# io_conn.net
KiCad netlist of a schematic drawn in Altium Designer
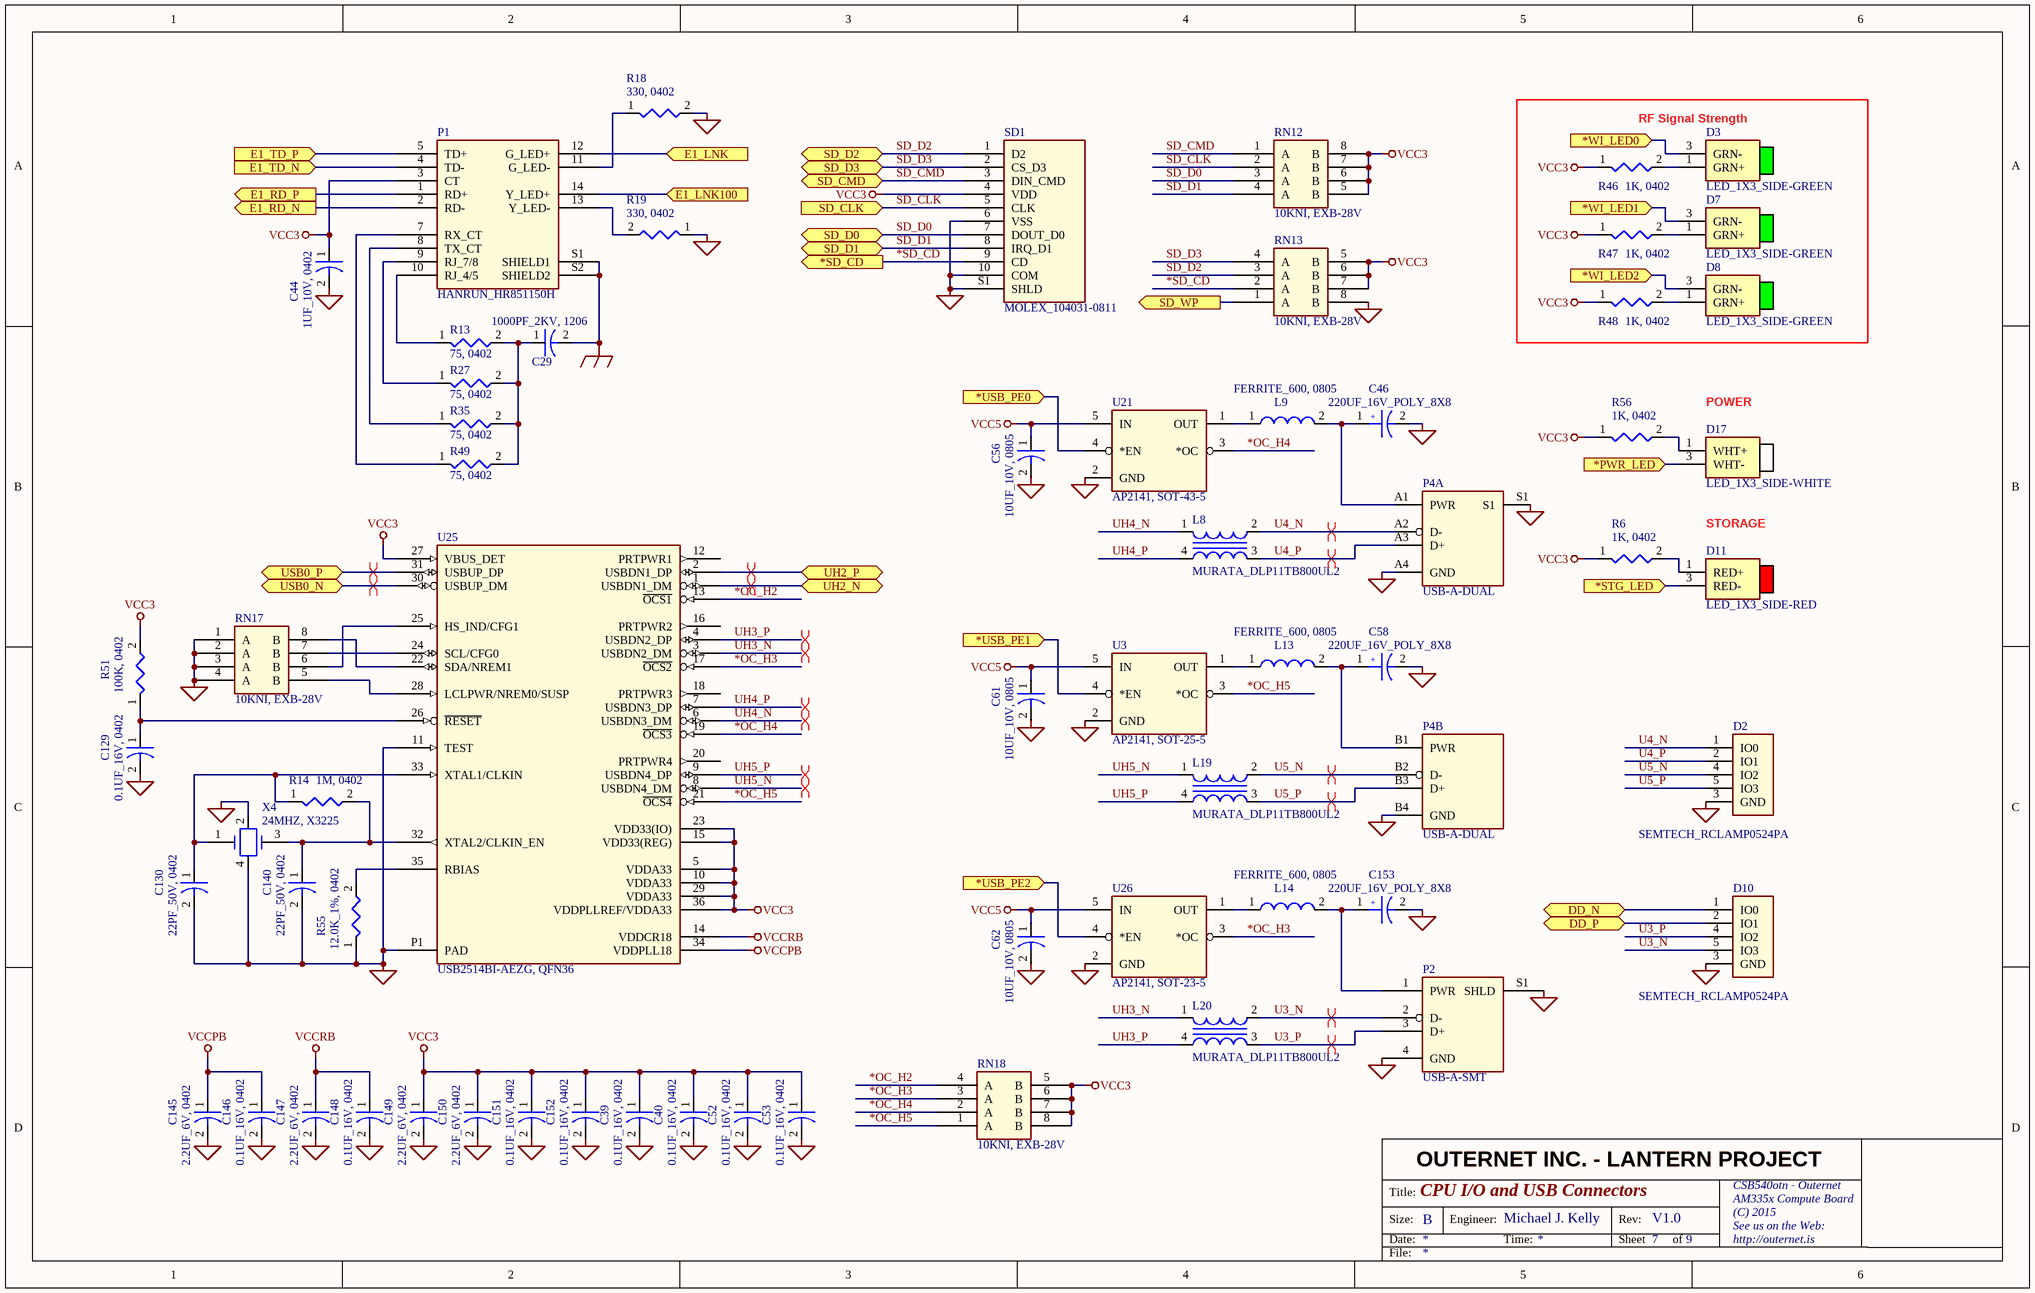
[diagram p0: io_conn.SchDoc]

(export (version "E")
  (design (tool "Eeschema 10.0.6"))
  (components
    (comp (ref "C29")
      (value "1000PF_2KV, 1206")
      (footprint "1206C")
      (description "CAP - 1206 PKG")
      (libsource (lib "COGENT_Library") (part "1000PF_2KV, 1206"))
    )
    (comp (ref "C39")
      (value "0.1UF_16V, 0402")
      (footprint "0402C")
      (description "CAP - 0402 PKG")
      (libsource (lib "COGENT_Library") (part "0.1UF_16V, 0402"))
    )
    (comp (ref "C40")
      (value "0.1UF_16V, 0402")
      (footprint "0402C")
      (description "CAP - 0402 PKG")
      (libsource (lib "COGENT_Library") (part "0.1UF_16V, 0402"))
    )
    (comp (ref "C44")
      (value "1UF_10V, 0402")
      (footprint "0402C")
      (description "CAP - 0402 PKG")
      (libsource (lib "COGENT_Library") (part "1UF_10V, 0402"))
    )
    (comp (ref "C46")
      (value "220UF_16V_POLY_8X8")
      (footprint "ELEC_8MM_8MM")
      (description "CAP - ELEC_POLY, 8mm x 8mm x 3.5mm")
      (libsource (lib "COGENT_Library") (part "220UF_16V_POLY_8X8"))
    )
    (comp (ref "C52")
      (value "0.1UF_16V, 0402")
      (footprint "0402C")
      (description "CAP - 0402 PKG")
      (libsource (lib "COGENT_Library") (part "0.1UF_16V, 0402"))
    )
    (comp (ref "C53")
      (value "0.1UF_16V, 0402")
      (footprint "0402C")
      (description "CAP - 0402 PKG")
      (libsource (lib "COGENT_Library") (part "0.1UF_16V, 0402"))
    )
    (comp (ref "C56")
      (value "10UF_10V, 0805")
      (footprint "0805C")
      (description "CAP - 0805 PKG")
      (libsource (lib "COGENT_Library") (part "10UF_10V, 0805"))
    )
    (comp (ref "C58")
      (value "220UF_16V_POLY_8X8")
      (footprint "ELEC_8MM_8MM")
      (description "CAP - ELEC_POLY, 8mm x 8mm x 3.5mm")
      (libsource (lib "COGENT_Library") (part "220UF_16V_POLY_8X8"))
    )
    (comp (ref "C61")
      (value "10UF_10V, 0805")
      (footprint "0805C")
      (description "CAP - 0805 PKG")
      (libsource (lib "COGENT_Library") (part "10UF_10V, 0805"))
    )
    (comp (ref "C62")
      (value "10UF_10V, 0805")
      (footprint "0805C")
      (description "CAP - 0805 PKG")
      (libsource (lib "COGENT_Library") (part "10UF_10V, 0805"))
    )
    (comp (ref "C129")
      (value "0.1UF_16V, 0402")
      (footprint "0402C")
      (description "CAP - 0402 PKG")
      (libsource (lib "COGENT_Library") (part "0.1UF_16V, 0402"))
    )
    (comp (ref "C130")
      (value "22PF_50V, 0402")
      (footprint "0402C")
      (description "CAP - 0402 PKG")
      (libsource (lib "COGENT_Library") (part "22PF_50V, 0402"))
    )
    (comp (ref "C140")
      (value "22PF_50V, 0402")
      (footprint "0402C")
      (description "CAP - 0402 PKG")
      (libsource (lib "COGENT_Library") (part "22PF_50V, 0402"))
    )
    (comp (ref "C145")
      (value "2.2UF_6V, 0402")
      (footprint "0402C")
      (description "CAP - 0402 PKG")
      (libsource (lib "COGENT_Library") (part "2.2UF_6V, 0402"))
    )
    (comp (ref "C146")
      (value "0.1UF_16V, 0402")
      (footprint "0402C")
      (description "CAP - 0402 PKG")
      (libsource (lib "COGENT_Library") (part "0.1UF_16V, 0402"))
    )
    (comp (ref "C147")
      (value "2.2UF_6V, 0402")
      (footprint "0402C")
      (description "CAP - 0402 PKG")
      (libsource (lib "COGENT_Library") (part "2.2UF_6V, 0402"))
    )
    (comp (ref "C148")
      (value "0.1UF_16V, 0402")
      (footprint "0402C")
      (description "CAP - 0402 PKG")
      (libsource (lib "COGENT_Library") (part "0.1UF_16V, 0402"))
    )
    (comp (ref "C149")
      (value "2.2UF_6V, 0402")
      (footprint "0402C")
      (description "CAP - 0402 PKG")
      (libsource (lib "COGENT_Library") (part "2.2UF_6V, 0402"))
    )
    (comp (ref "C150")
      (value "2.2UF_6V, 0402")
      (footprint "0402C")
      (description "CAP - 0402 PKG")
      (libsource (lib "COGENT_Library") (part "2.2UF_6V, 0402"))
    )
    (comp (ref "C151")
      (value "0.1UF_16V, 0402")
      (footprint "0402C")
      (description "CAP - 0402 PKG")
      (libsource (lib "COGENT_Library") (part "0.1UF_16V, 0402"))
    )
    (comp (ref "C152")
      (value "0.1UF_16V, 0402")
      (footprint "0402C")
      (description "CAP - 0402 PKG")
      (libsource (lib "COGENT_Library") (part "0.1UF_16V, 0402"))
    )
    (comp (ref "C153")
      (value "220UF_16V_POLY_8X8")
      (footprint "ELEC_8MM_8MM")
      (description "CAP - ELEC_POLY, 8mm x 8mm x 3.5mm")
      (libsource (lib "COGENT_Library") (part "220UF_16V_POLY_8X8"))
    )
    (comp (ref "D2")
      (value "SEMTECH_RCLAMP0524PA")
      (footprint "RCLAMP0524")
      (description "DIODE - TVS ARRAY, 0.3PF")
      (libsource (lib "COGENT_Library") (part "SEMTECH_RCLAMP0524PA"))
    )
    (comp (ref "D3")
      (value "LED_1X3_SIDE-GREEN")
      (footprint "LED_1X3_SIDE-GREEN")
      (description "LED - SIDEVIEW, SMT, GREEN")
      (libsource (lib "COGENT_Library") (part "LED_1X3_SIDE-GREEN"))
    )
    (comp (ref "D7")
      (value "LED_1X3_SIDE-GREEN")
      (footprint "LED_1X3_SIDE-GREEN")
      (description "LED - SIDEVIEW, SMT, GREEN")
      (libsource (lib "COGENT_Library") (part "LED_1X3_SIDE-GREEN"))
    )
    (comp (ref "D8")
      (value "LED_1X3_SIDE-GREEN")
      (footprint "LED_1X3_SIDE-GREEN")
      (description "LED - SIDEVIEW, SMT, GREEN")
      (libsource (lib "COGENT_Library") (part "LED_1X3_SIDE-GREEN"))
    )
    (comp (ref "D10")
      (value "SEMTECH_RCLAMP0524PA")
      (footprint "RCLAMP0524")
      (description "DIODE - TVS ARRAY, 0.3PF")
      (libsource (lib "COGENT_Library") (part "SEMTECH_RCLAMP0524PA"))
    )
    (comp (ref "D11")
      (value "LED_1X3_SIDE-RED")
      (footprint "LED_1X3_SIDE-RED")
      (description "LED - SIDEVIEW, SMT, RED")
      (libsource (lib "COGENT_Library") (part "LED_1X3_SIDE-RED"))
    )
    (comp (ref "D17")
      (value "LED_1X3_SIDE-WHITE")
      (footprint "LED_1X3_SIDE-WHITE")
      (description "LED - SIDEVIEW, SMT, WHITE")
      (libsource (lib "COGENT_Library") (part "LED_1X3_SIDE-WHITE"))
    )
    (comp (ref "L8")
      (value "MURATA_DLP11TB800UL2")
      (footprint "PANASONIC_EXC24C")
      (description "FERRITE - COMMON MODE FILTER, USB3, FILM")
      (libsource (lib "COGENT_Library") (part "MURATA_DLP11TB800UL2"))
    )
    (comp (ref "L9")
      (value "FERRITE_600, 0805")
      (footprint "0805L")
      (description "FERRITE BEAD - 600 OHM, 2A, 0805 PKG")
      (libsource (lib "COGENT_Library") (part "FERRITE_600, 0805"))
    )
    (comp (ref "L13")
      (value "FERRITE_600, 0805")
      (footprint "0805L")
      (description "FERRITE BEAD - 600 OHM, 2A, 0805 PKG")
      (libsource (lib "COGENT_Library") (part "FERRITE_600, 0805"))
    )
    (comp (ref "L14")
      (value "FERRITE_600, 0805")
      (footprint "0805L")
      (description "FERRITE BEAD - 600 OHM, 2A, 0805 PKG")
      (libsource (lib "COGENT_Library") (part "FERRITE_600, 0805"))
    )
    (comp (ref "L19")
      (value "MURATA_DLP11TB800UL2")
      (footprint "PANASONIC_EXC24C")
      (description "FERRITE - COMMON MODE FILTER, USB3, FILM")
      (libsource (lib "COGENT_Library") (part "MURATA_DLP11TB800UL2"))
    )
    (comp (ref "L20")
      (value "MURATA_DLP11TB800UL2")
      (footprint "PANASONIC_EXC24C")
      (description "FERRITE - COMMON MODE FILTER, USB3, FILM")
      (libsource (lib "COGENT_Library") (part "MURATA_DLP11TB800UL2"))
    )
    (comp (ref "P1")
      (value "HANRUN_HR851150H")
      (footprint "SPEEDTECH_P65-101-1HQ9")
      (description "CONN - RJ45 10/100 W/POE, SPEEDTECH")
      (libsource (lib "COGENT_Library") (part "HANRUN_HR851150H"))
    )
    (comp (ref "P2")
      (value "USB-A-SMT")
      (footprint "USB-A-SMT")
      (description "CONN - USB TYPE A SMT")
      (libsource (lib "COGENT_Library") (part "USB-A-SMT"))
    )
    (comp (ref "P4")
      (value "USB-A-DUAL")
      (footprint "USB-A-DUAL")
      (description "CONN - USB TYPE A - DUAL")
      (libsource (lib "COGENT_Library") (part "USB-A-DUAL"))
    )
    (comp (ref "R6")
      (value "1K, 0402")
      (footprint "0402R")
      (description "RES - 0402 PKG")
      (libsource (lib "COGENT_Library") (part "1K, 0402"))
    )
    (comp (ref "R13")
      (value "75, 0402")
      (footprint "0402R")
      (description "RES - 0402 PKG")
      (libsource (lib "COGENT_Library") (part "75, 0402"))
    )
    (comp (ref "R14")
      (value "1M, 0402")
      (footprint "0402R")
      (description "RES - 0402 PKG")
      (libsource (lib "COGENT_Library") (part "1M, 0402"))
    )
    (comp (ref "R18")
      (value "330, 0402")
      (footprint "0402R")
      (description "RES - 0402 PKG")
      (libsource (lib "COGENT_Library") (part "330, 0402"))
    )
    (comp (ref "R19")
      (value "330, 0402")
      (footprint "0402R")
      (description "RES - 0402 PKG")
      (libsource (lib "COGENT_Library") (part "330, 0402"))
    )
    (comp (ref "R27")
      (value "75, 0402")
      (footprint "0402R")
      (description "RES - 0402 PKG")
      (libsource (lib "COGENT_Library") (part "75, 0402"))
    )
    (comp (ref "R35")
      (value "75, 0402")
      (footprint "0402R")
      (description "RES - 0402 PKG")
      (libsource (lib "COGENT_Library") (part "75, 0402"))
    )
    (comp (ref "R46")
      (value "1K, 0402")
      (footprint "0402R")
      (description "RES - 0402 PKG")
      (libsource (lib "COGENT_Library") (part "1K, 0402"))
    )
    (comp (ref "R47")
      (value "1K, 0402")
      (footprint "0402R")
      (description "RES - 0402 PKG")
      (libsource (lib "COGENT_Library") (part "1K, 0402"))
    )
    (comp (ref "R48")
      (value "1K, 0402")
      (footprint "0402R")
      (description "RES - 0402 PKG")
      (libsource (lib "COGENT_Library") (part "1K, 0402"))
    )
    (comp (ref "R49")
      (value "75, 0402")
      (footprint "0402R")
      (description "RES - 0402 PKG")
      (libsource (lib "COGENT_Library") (part "75, 0402"))
    )
    (comp (ref "R51")
      (value "100K, 0402")
      (footprint "0402R")
      (description "RES - 0402 PKG")
      (libsource (lib "COGENT_Library") (part "100K, 0402"))
    )
    (comp (ref "R55")
      (value "12.0K_1%, 0402")
      (footprint "0402R")
      (description "RES - 0402 PKG")
      (libsource (lib "COGENT_Library") (part "12.0K_1%, 0402"))
    )
    (comp (ref "R56")
      (value "1K, 0402")
      (footprint "0402R")
      (description "RES - 0402 PKG")
      (libsource (lib "COGENT_Library") (part "1K, 0402"))
    )
    (comp (ref "RN12")
      (value "10KNI, EXB-28V")
      (footprint "EXB-28V")
      (description "RES NET, 4 INDIVIDUAL, EXB-28V")
      (libsource (lib "") (part "10KNI, EXB-28V_1"))
    )
    (comp (ref "RN13")
      (value "10KNI, EXB-28V")
      (footprint "EXB-28V")
      (description "RES NET, 4 INDIVIDUAL, EXB-28V")
      (libsource (lib "COGENT_Library") (part "10KNI, EXB-28V"))
    )
    (comp (ref "RN17")
      (value "10KNI, EXB-28V")
      (footprint "EXB-28V")
      (description "RES NET, 4 INDIVIDUAL, EXB-28V")
      (libsource (lib "") (part "10KNI, EXB-28V_1"))
    )
    (comp (ref "RN18")
      (value "10KNI, EXB-28V")
      (footprint "EXB-28V")
      (description "RES NET, 4 INDIVIDUAL, EXB-28V")
      (libsource (lib "COGENT_Library") (part "10KNI, EXB-28V"))
    )
    (comp (ref "SD1")
      (value "MOLEX_104031-0811")
      (footprint "MOLEX_104031-0811")
      (description "CONN - SD/MMC, MICRO, PUSH/PUSH, W/CD")
      (libsource (lib "COGENT_Library") (part "MOLEX_104031-0811"))
    )
    (comp (ref "U3")
      (value "AP2141, SOT-25-5")
      (footprint "SOT-23-5")
      (description "IC - POWER SWITCH, 500MA, LOW TRUE")
      (libsource (lib "COGENT_Library") (part "AP2141, SOT-23-5"))
    )
    (comp (ref "U21")
      (value "AP2141, SOT-43-5")
      (footprint "SOT-23-5")
      (description "IC - POWER SWITCH, 500MA, LOW TRUE")
      (libsource (lib "COGENT_Library") (part "AP2141, SOT-23-5"))
    )
    (comp (ref "U25")
      (value "USB2514BI-AEZG, QFN36")
      (footprint "QFN36")
      (description "USB - 2.0 HUB, FOUR PORT, I-TEMP")
      (libsource (lib "COGENT_Library") (part "USB2514BI-AEZG, QFN36"))
    )
    (comp (ref "U26")
      (value "AP2141, SOT-23-5")
      (footprint "SOT-23-5")
      (description "IC - POWER SWITCH, 500MA, LOW TRUE")
      (libsource (lib "COGENT_Library") (part "AP2141, SOT-23-5"))
    )
    (comp (ref "X4")
      (value "24MHZ, X3225")
      (footprint "X3225")
      (description "CRYSTAL - SMT, 3.2MM x 2.5MM, ABM8 PKG")
      (libsource (lib "COGENT_Library") (part "24MHZ, X3225"))
    )
  )
  (nets
    (net (code "1") (name "/*OC_H2") (class "Default")
      (node (ref "RN18") (pin "4") (pinfunction "A_4") (pintype "passive"))
      (node (ref "U25") (pin "13") (pinfunction "~{OCS1}_13") (pintype "input"))
    )
    (net (code "2") (name "/*OC_H3") (class "Default")
      (node (ref "RN18") (pin "3") (pinfunction "A_3") (pintype "passive"))
      (node (ref "U25") (pin "17") (pinfunction "~{OCS2}_17") (pintype "input"))
      (node (ref "U26") (pin "3") (pinfunction "*OC_3") (pintype "passive"))
    )
    (net (code "3") (name "/*OC_H4") (class "Default")
      (node (ref "RN18") (pin "2") (pinfunction "A_2") (pintype "passive"))
      (node (ref "U21") (pin "3") (pinfunction "*OC_3") (pintype "passive"))
      (node (ref "U25") (pin "19") (pinfunction "~{OCS3}_19") (pintype "input"))
    )
    (net (code "4") (name "/*OC_H5") (class "Default")
      (node (ref "RN18") (pin "1") (pinfunction "A_1") (pintype "passive"))
      (node (ref "U25") (pin "21") (pinfunction "~{OCS4}_21") (pintype "input"))
      (node (ref "U3") (pin "3") (pinfunction "*OC_3") (pintype "passive"))
    )
    (net (code "5") (name "/*PWR_LED") (class "Default")
      (node (ref "D17") (pin "3") (pinfunction "WHT-_3") (pintype "passive"))
    )
    (net (code "6") (name "/*SD_CD") (class "Default")
      (node (ref "RN13") (pin "2") (pinfunction "A_2") (pintype "passive"))
      (node (ref "SD1") (pin "9") (pinfunction "CD_9") (pintype "passive"))
    )
    (net (code "7") (name "/*STG_LED") (class "Default")
      (node (ref "D11") (pin "3") (pinfunction "RED-_3") (pintype "passive"))
    )
    (net (code "8") (name "/*USB_PE0") (class "Default")
      (node (ref "U21") (pin "4") (pinfunction "*EN_4") (pintype "passive"))
    )
    (net (code "9") (name "/*USB_PE1") (class "Default")
      (node (ref "U3") (pin "4") (pinfunction "*EN_4") (pintype "passive"))
    )
    (net (code "10") (name "/*USB_PE2") (class "Default")
      (node (ref "U26") (pin "4") (pinfunction "*EN_4") (pintype "passive"))
    )
    (net (code "11") (name "/*WI_LED0") (class "Default")
      (node (ref "D3") (pin "3") (pinfunction "GRN-_3") (pintype "passive"))
    )
    (net (code "12") (name "/*WI_LED1") (class "Default")
      (node (ref "D7") (pin "3") (pinfunction "GRN-_3") (pintype "passive"))
    )
    (net (code "13") (name "/*WI_LED2") (class "Default")
      (node (ref "D8") (pin "3") (pinfunction "GRN-_3") (pintype "passive"))
    )
    (net (code "14") (name "/DD_N") (class "Default")
      (node (ref "D10") (pin "1") (pinfunction "IO0_1") (pintype "passive"))
    )
    (net (code "15") (name "/DD_P") (class "Default")
      (node (ref "D10") (pin "2") (pinfunction "IO1_2") (pintype "passive"))
    )
    (net (code "16") (name "/E1_LNK") (class "Default")
      (node (ref "P1") (pin "12") (pinfunction "G_LED+_12") (pintype "passive"))
    )
    (net (code "17") (name "/E1_LNK100") (class "Default")
      (node (ref "P1") (pin "14") (pinfunction "Y_LED+_14") (pintype "passive"))
    )
    (net (code "18") (name "/E1_RD_N") (class "Default")
      (node (ref "P1") (pin "2") (pinfunction "RD-_2") (pintype "passive"))
    )
    (net (code "19") (name "/E1_RD_P") (class "Default")
      (node (ref "P1") (pin "1") (pinfunction "RD+_1") (pintype "passive"))
    )
    (net (code "20") (name "/E1_TD_N") (class "Default")
      (node (ref "P1") (pin "4") (pinfunction "TD-_4") (pintype "passive"))
    )
    (net (code "21") (name "/E1_TD_P") (class "Default")
      (node (ref "P1") (pin "5") (pinfunction "TD+_5") (pintype "passive"))
    )
    (net (code "22") (name "/SD_CLK") (class "Default")
      (node (ref "RN12") (pin "2") (pinfunction "A_2") (pintype "passive"))
      (node (ref "SD1") (pin "5") (pinfunction "CLK_5") (pintype "passive"))
    )
    (net (code "23") (name "/SD_CMD") (class "Default")
      (node (ref "RN12") (pin "1") (pinfunction "A_1") (pintype "passive"))
      (node (ref "SD1") (pin "3") (pinfunction "DIN_CMD_3") (pintype "passive"))
    )
    (net (code "24") (name "/SD_D0") (class "Default")
      (node (ref "RN12") (pin "3") (pinfunction "A_3") (pintype "passive"))
      (node (ref "SD1") (pin "7") (pinfunction "DOUT_D0_7") (pintype "passive"))
    )
    (net (code "25") (name "/SD_D1") (class "Default")
      (node (ref "RN12") (pin "4") (pinfunction "A_4") (pintype "passive"))
      (node (ref "SD1") (pin "8") (pinfunction "IRQ_D1_8") (pintype "passive"))
    )
    (net (code "26") (name "/SD_D2") (class "Default")
      (node (ref "RN13") (pin "3") (pinfunction "A_3") (pintype "passive"))
      (node (ref "SD1") (pin "1") (pinfunction "D2_1") (pintype "passive"))
    )
    (net (code "27") (name "/SD_D3") (class "Default")
      (node (ref "RN13") (pin "4") (pinfunction "A_4") (pintype "passive"))
      (node (ref "SD1") (pin "2") (pinfunction "CS_D3_2") (pintype "passive"))
    )
    (net (code "28") (name "/SD_WP") (class "Default")
      (node (ref "RN13") (pin "1") (pinfunction "A_1") (pintype "passive"))
    )
    (net (code "29") (name "/U3_N") (class "Default")
      (node (ref "D10") (pin "5") (pinfunction "IO3_5") (pintype "passive"))
      (node (ref "L20") (pin "2") (pinfunction "2_2") (pintype "passive"))
      (node (ref "P2") (pin "2") (pinfunction "D-_2") (pintype "passive"))
    )
    (net (code "30") (name "/U3_P") (class "Default")
      (node (ref "D10") (pin "4") (pinfunction "IO2_4") (pintype "passive"))
      (node (ref "L20") (pin "3") (pinfunction "3_3") (pintype "passive"))
      (node (ref "P2") (pin "3") (pinfunction "D+_3") (pintype "passive"))
    )
    (net (code "31") (name "/U4_N") (class "Default")
      (node (ref "D2") (pin "1") (pinfunction "IO0_1") (pintype "passive"))
      (node (ref "L8") (pin "2") (pinfunction "2_2") (pintype "passive"))
      (node (ref "P4") (pin "A2") (pinfunction "D-_A2") (pintype "tri_state"))
    )
    (net (code "32") (name "/U4_P") (class "Default")
      (node (ref "D2") (pin "2") (pinfunction "IO1_2") (pintype "passive"))
      (node (ref "L8") (pin "3") (pinfunction "3_3") (pintype "passive"))
      (node (ref "P4") (pin "A3") (pinfunction "D+_A3") (pintype "tri_state"))
    )
    (net (code "33") (name "/U5_N") (class "Default")
      (node (ref "D2") (pin "4") (pinfunction "IO2_4") (pintype "passive"))
      (node (ref "L19") (pin "2") (pinfunction "2_2") (pintype "passive"))
      (node (ref "P4") (pin "B2") (pinfunction "D-_B2") (pintype "tri_state"))
    )
    (net (code "34") (name "/U5_P") (class "Default")
      (node (ref "D2") (pin "5") (pinfunction "IO3_5") (pintype "passive"))
      (node (ref "L19") (pin "3") (pinfunction "3_3") (pintype "passive"))
      (node (ref "P4") (pin "B3") (pinfunction "D+_B3") (pintype "tri_state"))
    )
    (net (code "35") (name "/UH2_N") (class "Default")
      (node (ref "U25") (pin "1") (pinfunction "USBDN1_DM_1") (pintype "bidirectional"))
    )
    (net (code "36") (name "/UH2_P") (class "Default")
      (node (ref "U25") (pin "2") (pinfunction "USBDN1_DP_2") (pintype "bidirectional"))
    )
    (net (code "37") (name "/UH3_N") (class "Default")
      (node (ref "L20") (pin "1") (pinfunction "1_1") (pintype "passive"))
      (node (ref "U25") (pin "3") (pinfunction "USBDN2_DM_3") (pintype "bidirectional"))
    )
    (net (code "38") (name "/UH3_P") (class "Default")
      (node (ref "L20") (pin "4") (pinfunction "4_4") (pintype "passive"))
      (node (ref "U25") (pin "4") (pinfunction "USBDN2_DP_4") (pintype "bidirectional"))
    )
    (net (code "39") (name "/UH4_N") (class "Default")
      (node (ref "L8") (pin "1") (pinfunction "1_1") (pintype "passive"))
      (node (ref "U25") (pin "6") (pinfunction "USBDN3_DM_6") (pintype "bidirectional"))
    )
    (net (code "40") (name "/UH4_P") (class "Default")
      (node (ref "L8") (pin "4") (pinfunction "4_4") (pintype "passive"))
      (node (ref "U25") (pin "7") (pinfunction "USBDN3_DP_7") (pintype "bidirectional"))
    )
    (net (code "41") (name "/UH5_N") (class "Default")
      (node (ref "L19") (pin "1") (pinfunction "1_1") (pintype "passive"))
      (node (ref "U25") (pin "8") (pinfunction "USBDN4_DM_8") (pintype "bidirectional"))
    )
    (net (code "42") (name "/UH5_P") (class "Default")
      (node (ref "L19") (pin "4") (pinfunction "4_4") (pintype "passive"))
      (node (ref "U25") (pin "9") (pinfunction "USBDN4_DP_9") (pintype "bidirectional"))
    )
    (net (code "43") (name "/USB0_N") (class "Default")
      (node (ref "U25") (pin "30") (pinfunction "USBUP_DM_30") (pintype "bidirectional"))
    )
    (net (code "44") (name "/USB0_P") (class "Default")
      (node (ref "U25") (pin "31") (pinfunction "USBUP_DP_31") (pintype "bidirectional"))
    )
    (net (code "45") (name "EARTH") (class "Default")
      (node (ref "C29") (pin "2") (pinfunction "2_2") (pintype "passive"))
      (node (ref "P1") (pin "S1") (pinfunction "SHIELD1_S1") (pintype "passive"))
      (node (ref "P1") (pin "S2") (pinfunction "SHIELD2_S2") (pintype "passive"))
    )
    (net (code "46") (name "GND") (class "Default")
      (node (ref "C129") (pin "2") (pinfunction "2_2") (pintype "passive"))
      (node (ref "C130") (pin "2") (pinfunction "2_2") (pintype "passive"))
      (node (ref "C140") (pin "2") (pinfunction "2_2") (pintype "passive"))
      (node (ref "C145") (pin "2") (pinfunction "2_2") (pintype "passive"))
      (node (ref "C146") (pin "2") (pinfunction "2_2") (pintype "passive"))
      (node (ref "C147") (pin "2") (pinfunction "2_2") (pintype "passive"))
      (node (ref "C148") (pin "2") (pinfunction "2_2") (pintype "passive"))
      (node (ref "C149") (pin "2") (pinfunction "2_2") (pintype "passive"))
      (node (ref "C150") (pin "2") (pinfunction "2_2") (pintype "passive"))
      (node (ref "C151") (pin "2") (pinfunction "2_2") (pintype "passive"))
      (node (ref "C152") (pin "2") (pinfunction "2_2") (pintype "passive"))
      (node (ref "C153") (pin "2") (pinfunction "2_2") (pintype "passive"))
      (node (ref "C39") (pin "2") (pinfunction "2_2") (pintype "passive"))
      (node (ref "C40") (pin "2") (pinfunction "2_2") (pintype "passive"))
      (node (ref "C44") (pin "2") (pinfunction "2_2") (pintype "passive"))
      (node (ref "C46") (pin "2") (pinfunction "2_2") (pintype "passive"))
      (node (ref "C52") (pin "2") (pinfunction "2_2") (pintype "passive"))
      (node (ref "C53") (pin "2") (pinfunction "2_2") (pintype "passive"))
      (node (ref "C56") (pin "2") (pinfunction "2_2") (pintype "passive"))
      (node (ref "C58") (pin "2") (pinfunction "2_2") (pintype "passive"))
      (node (ref "C61") (pin "2") (pinfunction "2_2") (pintype "passive"))
      (node (ref "C62") (pin "2") (pinfunction "2_2") (pintype "passive"))
      (node (ref "D10") (pin "3") (pinfunction "GND_3") (pintype "passive"))
      (node (ref "D2") (pin "3") (pinfunction "GND_3") (pintype "passive"))
      (node (ref "P2") (pin "4") (pinfunction "GND_4") (pintype "power_in"))
      (node (ref "P2") (pin "S1") (pinfunction "SHLD_S1") (pintype "passive"))
      (node (ref "P4") (pin "A4") (pinfunction "GND_A4") (pintype "power_in"))
      (node (ref "P4") (pin "B4") (pinfunction "GND_B4") (pintype "power_in"))
      (node (ref "P4") (pin "S1") (pinfunction "S1_S1") (pintype "passive"))
      (node (ref "R18") (pin "2") (pinfunction "2_2") (pintype "passive"))
      (node (ref "R19") (pin "1") (pinfunction "1_1") (pintype "passive"))
      (node (ref "R55") (pin "1") (pinfunction "1_1") (pintype "passive"))
      (node (ref "RN13") (pin "8") (pinfunction "B_8") (pintype "passive"))
      (node (ref "RN17") (pin "1") (pinfunction "A_1") (pintype "passive"))
      (node (ref "RN17") (pin "2") (pinfunction "A_2") (pintype "passive"))
      (node (ref "RN17") (pin "3") (pinfunction "A_3") (pintype "passive"))
      (node (ref "RN17") (pin "4") (pinfunction "A_4") (pintype "passive"))
      (node (ref "SD1") (pin "10") (pinfunction "COM_10") (pintype "passive"))
      (node (ref "SD1") (pin "6") (pinfunction "VSS_6") (pintype "passive"))
      (node (ref "SD1") (pin "S1") (pinfunction "SHLD_S1") (pintype "passive"))
      (node (ref "U21") (pin "2") (pinfunction "GND_2") (pintype "passive"))
      (node (ref "U25") (pin "11") (pinfunction "TEST_11") (pintype "input"))
      (node (ref "U25") (pin "P1") (pinfunction "PAD_P1") (pintype "power_in"))
      (node (ref "U26") (pin "2") (pinfunction "GND_2") (pintype "passive"))
      (node (ref "U3") (pin "2") (pinfunction "GND_2") (pintype "passive"))
      (node (ref "X4") (pin "2") (pinfunction "2_2") (pintype "passive"))
      (node (ref "X4") (pin "4") (pinfunction "4_4") (pintype "passive"))
    )
    (net (code "47") (name "Net-(C29-Pad1)") (class "Default")
      (node (ref "C29") (pin "1") (pinfunction "1_1") (pintype "passive"))
      (node (ref "R13") (pin "2") (pinfunction "2_2") (pintype "passive"))
      (node (ref "R27") (pin "2") (pinfunction "2_2") (pintype "passive"))
      (node (ref "R35") (pin "2") (pinfunction "2_2") (pintype "passive"))
      (node (ref "R49") (pin "2") (pinfunction "2_2") (pintype "passive"))
    )
    (net (code "48") (name "Net-(D3-GRN+)") (class "Default")
      (node (ref "D3") (pin "1") (pinfunction "GRN+_1") (pintype "passive"))
      (node (ref "R46") (pin "2") (pinfunction "2_2") (pintype "passive"))
    )
    (net (code "49") (name "Net-(D7-GRN+)") (class "Default")
      (node (ref "D7") (pin "1") (pinfunction "GRN+_1") (pintype "passive"))
      (node (ref "R47") (pin "2") (pinfunction "2_2") (pintype "passive"))
    )
    (net (code "50") (name "Net-(D8-GRN+)") (class "Default")
      (node (ref "D8") (pin "1") (pinfunction "GRN+_1") (pintype "passive"))
      (node (ref "R48") (pin "2") (pinfunction "2_2") (pintype "passive"))
    )
    (net (code "51") (name "Net-(D11-RED+)") (class "Default")
      (node (ref "D11") (pin "1") (pinfunction "RED+_1") (pintype "passive"))
      (node (ref "R6") (pin "2") (pinfunction "2_2") (pintype "passive"))
    )
    (net (code "52") (name "Net-(D17-WHT+)") (class "Default")
      (node (ref "D17") (pin "1") (pinfunction "WHT+_1") (pintype "passive"))
      (node (ref "R56") (pin "2") (pinfunction "2_2") (pintype "passive"))
    )
    (net (code "53") (name "Net-(P1-G_LED-)") (class "Default")
      (node (ref "P1") (pin "11") (pinfunction "G_LED-_11") (pintype "passive"))
      (node (ref "R18") (pin "1") (pinfunction "1_1") (pintype "passive"))
    )
    (net (code "54") (name "Net-(P1-RJ_4{slash}5)") (class "Default")
      (node (ref "P1") (pin "10") (pinfunction "RJ_4/5_10") (pintype "passive"))
      (node (ref "R13") (pin "1") (pinfunction "1_1") (pintype "passive"))
    )
    (net (code "55") (name "Net-(P1-RJ_7{slash}8)") (class "Default")
      (node (ref "P1") (pin "9") (pinfunction "RJ_7/8_9") (pintype "passive"))
      (node (ref "R27") (pin "1") (pinfunction "1_1") (pintype "passive"))
    )
    (net (code "56") (name "Net-(P1-RX_CT)") (class "Default")
      (node (ref "P1") (pin "7") (pinfunction "RX_CT_7") (pintype "passive"))
      (node (ref "R49") (pin "1") (pinfunction "1_1") (pintype "passive"))
    )
    (net (code "57") (name "Net-(P1-TX_CT)") (class "Default")
      (node (ref "P1") (pin "8") (pinfunction "TX_CT_8") (pintype "passive"))
      (node (ref "R35") (pin "1") (pinfunction "1_1") (pintype "passive"))
    )
    (net (code "58") (name "Net-(P1-Y_LED-)") (class "Default")
      (node (ref "P1") (pin "13") (pinfunction "Y_LED-_13") (pintype "passive"))
      (node (ref "R19") (pin "2") (pinfunction "2_2") (pintype "passive"))
    )
    (net (code "59") (name "Net-(P2-PWR)") (class "Default")
      (node (ref "C153") (pin "1") (pinfunction "1_1") (pintype "passive"))
      (node (ref "L14") (pin "2") (pinfunction "2_2") (pintype "passive"))
      (node (ref "P2") (pin "1") (pinfunction "PWR_1") (pintype "power_in"))
    )
    (net (code "60") (name "Net-(P4A-PWR)") (class "Default")
      (node (ref "C46") (pin "1") (pinfunction "1_1") (pintype "passive"))
      (node (ref "L9") (pin "2") (pinfunction "2_2") (pintype "passive"))
      (node (ref "P4") (pin "A1") (pinfunction "PWR_A1") (pintype "power_in"))
    )
    (net (code "61") (name "Net-(P4B-PWR)") (class "Default")
      (node (ref "C58") (pin "1") (pinfunction "1_1") (pintype "passive"))
      (node (ref "L13") (pin "2") (pinfunction "2_2") (pintype "passive"))
      (node (ref "P4") (pin "B1") (pinfunction "PWR_B1") (pintype "power_in"))
    )
    (net (code "62") (name "Net-(U3-OUT)") (class "Default")
      (node (ref "L13") (pin "1") (pinfunction "1_1") (pintype "passive"))
      (node (ref "U3") (pin "1") (pinfunction "OUT_1") (pintype "passive"))
    )
    (net (code "63") (name "Net-(U21-OUT)") (class "Default")
      (node (ref "L9") (pin "1") (pinfunction "1_1") (pintype "passive"))
      (node (ref "U21") (pin "1") (pinfunction "OUT_1") (pintype "passive"))
    )
    (net (code "64") (name "Net-(U25-HS_IND{slash}CFG1)") (class "Default")
      (node (ref "RN17") (pin "6") (pinfunction "B_6") (pintype "passive"))
      (node (ref "U25") (pin "25") (pinfunction "HS_IND/CFG1_25") (pintype "input"))
    )
    (net (code "65") (name "Net-(U25-LCLPWR{slash}NREM0{slash}SUSP)") (class "Default")
      (node (ref "RN17") (pin "5") (pinfunction "B_5") (pintype "passive"))
      (node (ref "U25") (pin "28") (pinfunction "LCLPWR/NREM0/SUSP_28") (pintype "input"))
    )
    (net (code "66") (name "Net-(U25-RBIAS)") (class "Default")
      (node (ref "R55") (pin "2") (pinfunction "2_2") (pintype "passive"))
      (node (ref "U25") (pin "35") (pinfunction "RBIAS_35") (pintype "passive"))
    )
    (net (code "67") (name "Net-(U25-SCL{slash}CFG0)") (class "Default")
      (node (ref "RN17") (pin "7") (pinfunction "B_7") (pintype "passive"))
      (node (ref "U25") (pin "24") (pinfunction "SCL/CFG0_24") (pintype "bidirectional"))
    )
    (net (code "68") (name "Net-(U25-SDA{slash}NREM1)") (class "Default")
      (node (ref "RN17") (pin "8") (pinfunction "B_8") (pintype "passive"))
      (node (ref "U25") (pin "22") (pinfunction "SDA/NREM1_22") (pintype "bidirectional"))
    )
    (net (code "69") (name "Net-(U25-XTAL1{slash}CLKIN)") (class "Default")
      (node (ref "C130") (pin "1") (pinfunction "1_1") (pintype "passive"))
      (node (ref "R14") (pin "1") (pinfunction "1_1") (pintype "passive"))
      (node (ref "U25") (pin "33") (pinfunction "XTAL1/CLKIN_33") (pintype "input"))
      (node (ref "X4") (pin "1") (pinfunction "1_1") (pintype "passive"))
    )
    (net (code "70") (name "Net-(U25-XTAL2{slash}CLKIN_EN)") (class "Default")
      (node (ref "C140") (pin "1") (pinfunction "1_1") (pintype "passive"))
      (node (ref "R14") (pin "2") (pinfunction "2_2") (pintype "passive"))
      (node (ref "U25") (pin "32") (pinfunction "XTAL2/CLKIN_EN_32") (pintype "output"))
      (node (ref "X4") (pin "3") (pinfunction "3_3") (pintype "passive"))
    )
    (net (code "71") (name "Net-(U25-~{RESET})") (class "Default")
      (node (ref "C129") (pin "1") (pinfunction "1_1") (pintype "passive"))
      (node (ref "R51") (pin "1") (pinfunction "1_1") (pintype "passive"))
      (node (ref "U25") (pin "26") (pinfunction "~{RESET}_26") (pintype "input"))
    )
    (net (code "72") (name "Net-(U26-OUT)") (class "Default")
      (node (ref "L14") (pin "1") (pinfunction "1_1") (pintype "passive"))
      (node (ref "U26") (pin "1") (pinfunction "OUT_1") (pintype "passive"))
    )
    (net (code "73") (name "VCC3") (class "Default")
      (node (ref "C149") (pin "1") (pinfunction "1_1") (pintype "passive"))
      (node (ref "C150") (pin "1") (pinfunction "1_1") (pintype "passive"))
      (node (ref "C151") (pin "1") (pinfunction "1_1") (pintype "passive"))
      (node (ref "C152") (pin "1") (pinfunction "1_1") (pintype "passive"))
      (node (ref "C39") (pin "1") (pinfunction "1_1") (pintype "passive"))
      (node (ref "C40") (pin "1") (pinfunction "1_1") (pintype "passive"))
      (node (ref "C44") (pin "1") (pinfunction "1_1") (pintype "passive"))
      (node (ref "C52") (pin "1") (pinfunction "1_1") (pintype "passive"))
      (node (ref "C53") (pin "1") (pinfunction "1_1") (pintype "passive"))
      (node (ref "P1") (pin "3") (pinfunction "CT_3") (pintype "passive"))
      (node (ref "R46") (pin "1") (pinfunction "1_1") (pintype "passive"))
      (node (ref "R47") (pin "1") (pinfunction "1_1") (pintype "passive"))
      (node (ref "R48") (pin "1") (pinfunction "1_1") (pintype "passive"))
      (node (ref "R51") (pin "2") (pinfunction "2_2") (pintype "passive"))
      (node (ref "R56") (pin "1") (pinfunction "1_1") (pintype "passive"))
      (node (ref "R6") (pin "1") (pinfunction "1_1") (pintype "passive"))
      (node (ref "RN12") (pin "5") (pinfunction "B_5") (pintype "passive"))
      (node (ref "RN12") (pin "6") (pinfunction "B_6") (pintype "passive"))
      (node (ref "RN12") (pin "7") (pinfunction "B_7") (pintype "passive"))
      (node (ref "RN12") (pin "8") (pinfunction "B_8") (pintype "passive"))
      (node (ref "RN13") (pin "5") (pinfunction "B_5") (pintype "passive"))
      (node (ref "RN13") (pin "6") (pinfunction "B_6") (pintype "passive"))
      (node (ref "RN13") (pin "7") (pinfunction "B_7") (pintype "passive"))
      (node (ref "RN18") (pin "5") (pinfunction "B_5") (pintype "passive"))
      (node (ref "RN18") (pin "6") (pinfunction "B_6") (pintype "passive"))
      (node (ref "RN18") (pin "7") (pinfunction "B_7") (pintype "passive"))
      (node (ref "RN18") (pin "8") (pinfunction "B_8") (pintype "passive"))
      (node (ref "SD1") (pin "4") (pinfunction "VDD_4") (pintype "passive"))
      (node (ref "U25") (pin "10") (pinfunction "VDDA33_10") (pintype "power_in"))
      (node (ref "U25") (pin "15") (pinfunction "VDD33(REG)_15") (pintype "power_in"))
      (node (ref "U25") (pin "23") (pinfunction "VDD33(IO)_23") (pintype "power_in"))
      (node (ref "U25") (pin "27") (pinfunction "VBUS_DET_27") (pintype "input"))
      (node (ref "U25") (pin "29") (pinfunction "VDDA33_29") (pintype "power_in"))
      (node (ref "U25") (pin "36") (pinfunction "VDDPLLREF/VDDA33_36") (pintype "power_in"))
      (node (ref "U25") (pin "5") (pinfunction "VDDA33_5") (pintype "power_in"))
    )
    (net (code "74") (name "VCC5") (class "Default")
      (node (ref "C56") (pin "1") (pinfunction "1_1") (pintype "passive"))
      (node (ref "C61") (pin "1") (pinfunction "1_1") (pintype "passive"))
      (node (ref "C62") (pin "1") (pinfunction "1_1") (pintype "passive"))
      (node (ref "U21") (pin "5") (pinfunction "IN_5") (pintype "passive"))
      (node (ref "U26") (pin "5") (pinfunction "IN_5") (pintype "passive"))
      (node (ref "U3") (pin "5") (pinfunction "IN_5") (pintype "passive"))
    )
    (net (code "75") (name "VCCPB") (class "Default")
      (node (ref "C145") (pin "1") (pinfunction "1_1") (pintype "passive"))
      (node (ref "C146") (pin "1") (pinfunction "1_1") (pintype "passive"))
      (node (ref "U25") (pin "34") (pinfunction "VDDPLL18_34") (pintype "power_in"))
    )
    (net (code "76") (name "VCCRB") (class "Default")
      (node (ref "C147") (pin "1") (pinfunction "1_1") (pintype "passive"))
      (node (ref "C148") (pin "1") (pinfunction "1_1") (pintype "passive"))
      (node (ref "U25") (pin "14") (pinfunction "VDDCR18_14") (pintype "power_in"))
    )
    (net (code "77") (name "unconnected-(U25-PRTPWR1-Pad12)") (class "Default")
      (node (ref "U25") (pin "12") (pinfunction "PRTPWR1_12") (pintype "output"))
    )
    (net (code "78") (name "unconnected-(U25-PRTPWR2-Pad16)") (class "Default")
      (node (ref "U25") (pin "16") (pinfunction "PRTPWR2_16") (pintype "output"))
    )
    (net (code "79") (name "unconnected-(U25-PRTPWR3-Pad18)") (class "Default")
      (node (ref "U25") (pin "18") (pinfunction "PRTPWR3_18") (pintype "output"))
    )
    (net (code "80") (name "unconnected-(U25-PRTPWR4-Pad20)") (class "Default")
      (node (ref "U25") (pin "20") (pinfunction "PRTPWR4_20") (pintype "output"))
    )
  )
)
